# StuderA80ReproExtend_V0_3_XLR.net
KiCad netlist of a schematic drawn in Altium Designer
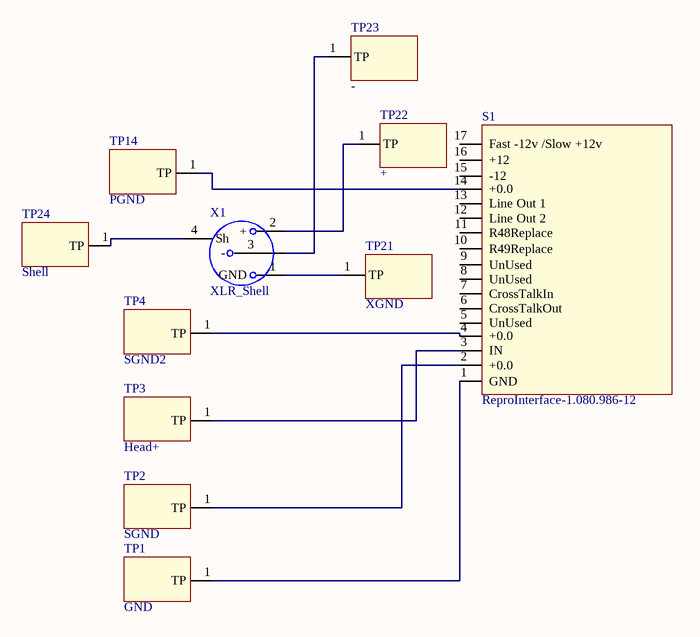
[diagram p0: StuderA80ReproExtend_V0.3_XLR.SchDoc]

(export (version "E")
  (design (tool "Eeschema 10.0.6"))
  (components
    (comp (ref "S1")
      (value "ReproInterface-1.080.986-12")
      (footprint "ReproInterface")
      (description "Studer A80 RC Reproduce Card 1.080.986-12 Interface")
      (libsource (lib "Studer") (part "ReproInterface-1.080.986-12"))
    )
    (comp (ref "TP1") (value "GND") (footprint "TP-1.0mm") (libsource (lib "Studer") (part "TestPoint")))
    (comp (ref "TP2") (value "SGND") (footprint "TP-1.0mm") (libsource (lib "Studer") (part "TestPoint")))
    (comp (ref "TP3") (value "Head+") (footprint "TP-1.0mm") (libsource (lib "Studer") (part "TestPoint")))
    (comp (ref "TP4") (value "SGND2") (footprint "TP-1.0mm") (libsource (lib "Studer") (part "TestPoint")))
    (comp (ref "TP14") (value "PGND") (footprint "TP-1.0mm") (libsource (lib "Studer") (part "TestPoint")))
    (comp (ref "TP21") (value "XGND") (footprint "TP-1.0mm") (libsource (lib "") (part "TestPoint_1")))
    (comp (ref "TP22") (value "+") (footprint "TP-1.0mm") (libsource (lib "") (part "TestPoint_1")))
    (comp (ref "TP23") (value "-") (footprint "TP-1.0mm") (libsource (lib "") (part "TestPoint_1")))
    (comp (ref "TP24") (value "Shell") (footprint "TP-1.0mm") (libsource (lib "Studer") (part "TestPoint")))
    (comp (ref "X1")
      (value "XLR_Shell")
      (footprint "Neutrik-NC3FAAH-Shell")
      (description "3 Pin XLR with Shell Pin")
      (libsource (lib "Connectors") (part "XLR_Shell"))
    )
  )
  (nets
    (net (code "1") (name "Net-(S1-GND)") (class "Default")
      (node (ref "S1") (pin "1") (pinfunction "GND_1") (pintype "passive"))
      (node (ref "TP1") (pin "1") (pinfunction "TP_1") (pintype "passive"))
    )
    (net (code "2") (name "Net-(S1-IN)") (class "Default")
      (node (ref "S1") (pin "3") (pinfunction "IN_3") (pintype "passive"))
      (node (ref "TP3") (pin "1") (pinfunction "TP_1") (pintype "passive"))
    )
    (net (code "3") (name "Net-(TP2-TP)") (class "Default")
      (node (ref "S1") (pin "2") (pinfunction "+0.0_2") (pintype "passive"))
      (node (ref "TP2") (pin "1") (pinfunction "TP_1") (pintype "passive"))
    )
    (net (code "4") (name "Net-(TP4-TP)") (class "Default")
      (node (ref "S1") (pin "4") (pinfunction "+0.0_4") (pintype "passive"))
      (node (ref "TP4") (pin "1") (pinfunction "TP_1") (pintype "passive"))
    )
    (net (code "5") (name "Net-(TP14-TP)") (class "Default")
      (node (ref "S1") (pin "14") (pinfunction "+0.0_14") (pintype "passive"))
      (node (ref "TP14") (pin "1") (pinfunction "TP_1") (pintype "passive"))
    )
    (net (code "6") (name "Net-(TP21-TP)") (class "Default")
      (node (ref "TP21") (pin "1") (pinfunction "TP_1") (pintype "passive"))
      (node (ref "X1") (pin "1") (pinfunction "GND_1") (pintype "passive"))
    )
    (net (code "7") (name "Net-(TP22-TP)") (class "Default")
      (node (ref "TP22") (pin "1") (pinfunction "TP_1") (pintype "passive"))
      (node (ref "X1") (pin "2") (pinfunction "+_2") (pintype "passive"))
    )
    (net (code "8") (name "Net-(TP23-TP)") (class "Default")
      (node (ref "TP23") (pin "1") (pinfunction "TP_1") (pintype "passive"))
      (node (ref "X1") (pin "3") (pinfunction "-_3") (pintype "passive"))
    )
    (net (code "9") (name "Net-(TP24-TP)") (class "Default")
      (node (ref "TP24") (pin "1") (pinfunction "TP_1") (pintype "passive"))
      (node (ref "X1") (pin "4") (pinfunction "Sh_4") (pintype "passive"))
    )
    (net (code "10") (name "unconnected-(S1-+12-Pad16)") (class "Default")
      (node (ref "S1") (pin "16") (pinfunction "+12_16") (pintype "passive"))
    )
    (net (code "11") (name "unconnected-(S1--12-Pad15)") (class "Default")
      (node (ref "S1") (pin "15") (pinfunction "-12_15") (pintype "passive"))
    )
    (net (code "12") (name "unconnected-(S1-CrossTalkIn-Pad7)") (class "Default")
      (node (ref "S1") (pin "7") (pinfunction "CrossTalkIn_7") (pintype "passive"))
    )
    (net (code "13") (name "unconnected-(S1-CrossTalkOut-Pad6)") (class "Default")
      (node (ref "S1") (pin "6") (pinfunction "CrossTalkOut_6") (pintype "passive"))
    )
    (net (code "14") (name "unconnected-(S1-Fast_-12v_{slash}Slow_+12v-Pad17)") (class "Default")
      (node (ref "S1") (pin "17") (pinfunction "Fast_-12v_/Slow_+12v_17") (pintype "passive"))
    )
    (net (code "15") (name "unconnected-(S1-Line_Out_1-Pad13)") (class "Default")
      (node (ref "S1") (pin "13") (pinfunction "Line_Out_1_13") (pintype "passive"))
    )
    (net (code "16") (name "unconnected-(S1-Line_Out_2-Pad12)") (class "Default")
      (node (ref "S1") (pin "12") (pinfunction "Line_Out_2_12") (pintype "passive"))
    )
    (net (code "17") (name "unconnected-(S1-R48Replace-Pad11)") (class "Default")
      (node (ref "S1") (pin "11") (pinfunction "R48Replace_11") (pintype "passive"))
    )
    (net (code "18") (name "unconnected-(S1-R49Replace-Pad10)") (class "Default")
      (node (ref "S1") (pin "10") (pinfunction "R49Replace_10") (pintype "passive"))
    )
    (net (code "19") (name "unconnected-(S1-UnUsed-Pad5)") (class "Default")
      (node (ref "S1") (pin "5") (pinfunction "UnUsed_5") (pintype "passive"))
    )
    (net (code "20") (name "unconnected-(S1-UnUsed-Pad8)") (class "Default")
      (node (ref "S1") (pin "8") (pinfunction "UnUsed_8") (pintype "passive"))
    )
    (net (code "21") (name "unconnected-(S1-UnUsed-Pad9)") (class "Default")
      (node (ref "S1") (pin "9") (pinfunction "UnUsed_9") (pintype "passive"))
    )
  )
)
